# RGB_Logical_Shifter_Sheet.net
KiCad netlist of a schematic drawn in Altium Designer
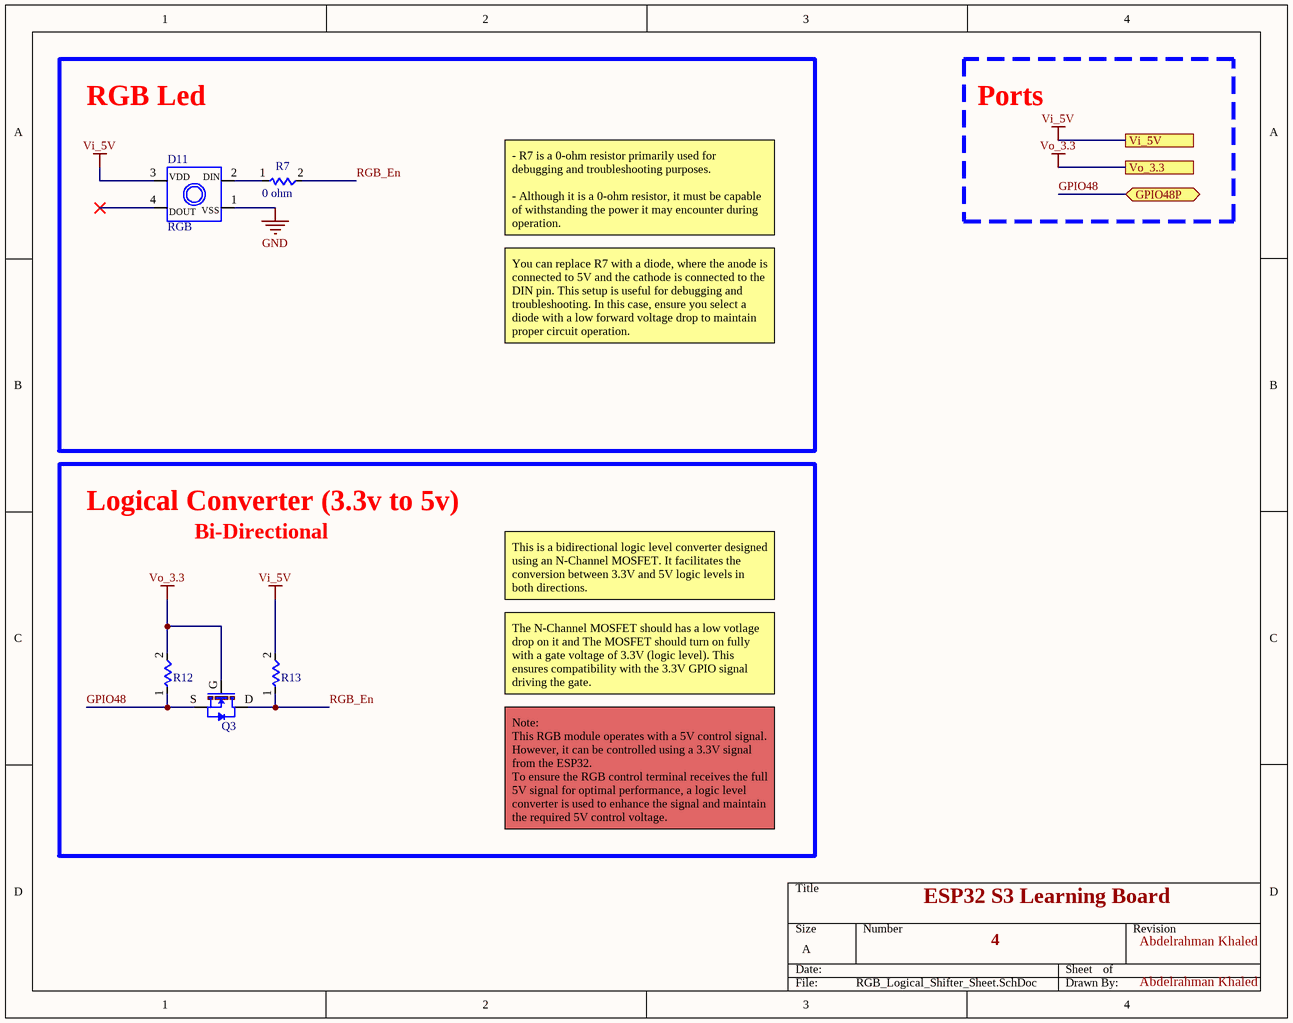
[diagram p0: RGB_Logical_Shifter_Sheet.SchDoc]

(export (version "E")
  (design (tool "Eeschema 10.0.6"))
  (components
    (comp (ref "D11")
      (value "RGB")
      (footprint "RGB")
      (description "LED RGB CLEAR 3528 SMD")
      (libsource (lib "ESP32_S3_Integrated_Library") (part "RGB"))
    )
    (comp (ref "Q3")
      (value "MOSFET_BSS138")
      (footprint "MOSFET_BSS138")
      (description "MOSFET N-CH 50V 220MA SOT23")
      (libsource (lib "ESP32_S3_Integrated_Library") (part "MOSFET_BSS138"))
    )
    (comp (ref "R7")
      (value "0 ohm")
      (footprint "Resistor")
      (description "Fuse Reseitance")
      (libsource (lib "ESP32_S3_Integrated_Library") (part "Resistance"))
    )
    (comp (ref "R12")
      (value "10K ohm")
      (footprint "Resistor")
      (description "Fuse Reseitance")
      (libsource (lib "ESP32_S3_Integrated_Library") (part "Resistance"))
    )
    (comp (ref "R13")
      (value "10K ohm")
      (footprint "Resistor")
      (description "Fuse Reseitance")
      (libsource (lib "ESP32_S3_Integrated_Library") (part "Resistance"))
    )
  )
  (nets
    (net (code "1") (name "/GPIO48") (class "Default")
      (node (ref "Q3") (pin "S") (pintype "passive"))
      (node (ref "R12") (pin "1") (pinfunction "Pin_1_1") (pintype "passive"))
    )
    (net (code "2") (name "/RGB_En") (class "Default")
      (node (ref "Q3") (pin "D") (pintype "passive"))
      (node (ref "R13") (pin "1") (pinfunction "Pin_1_1") (pintype "passive"))
      (node (ref "R7") (pin "2") (pinfunction "pin_2_2") (pintype "passive"))
    )
    (net (code "3") (name "GND") (class "Default") (node (ref "D11") (pin "1") (pintype "passive")))
    (net (code "4") (name "Net-(R7-Pin_1)") (class "Default")
      (node (ref "D11") (pin "2") (pintype "passive"))
      (node (ref "R7") (pin "1") (pinfunction "Pin_1_1") (pintype "passive"))
    )
    (net (code "5") (name "Vi_5V") (class "Default")
      (node (ref "D11") (pin "3") (pintype "passive"))
      (node (ref "R13") (pin "2") (pinfunction "pin_2_2") (pintype "passive"))
    )
    (net (code "6") (name "Vo_3.3") (class "Default")
      (node (ref "Q3") (pin "G") (pintype "passive"))
      (node (ref "R12") (pin "2") (pinfunction "pin_2_2") (pintype "passive"))
    )
    (net (code "7") (name "unconnected-(D11-Pad4)") (class "Default")
      (node (ref "D11") (pin "4") (pintype "passive+no_connect"))
    )
  )
)
